# LB_BIT_o6_BUZZER-v02_rev1.net
KiCad netlist of a schematic drawn in EAGLE
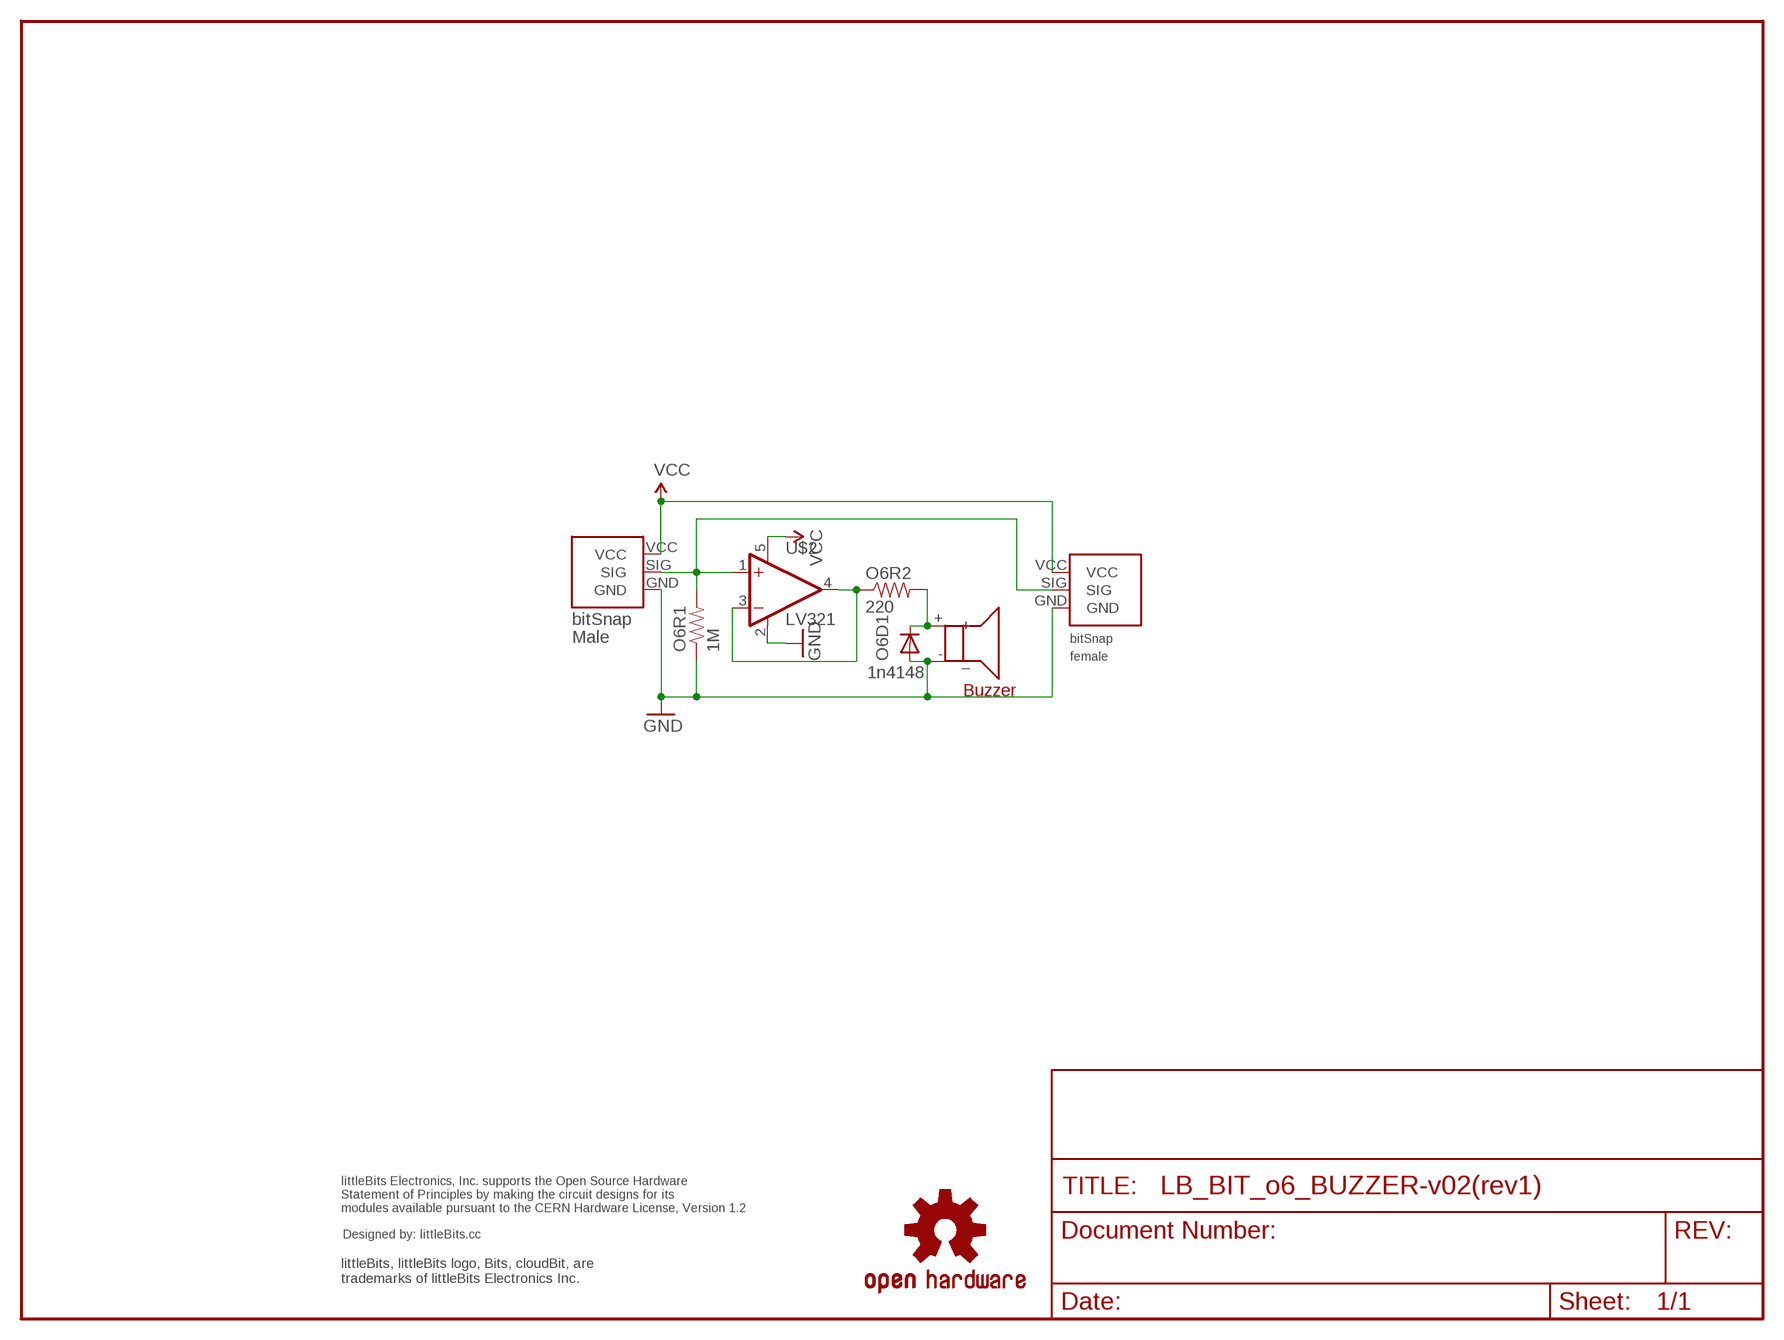
[diagram p0: schematic, sheet 1]

(export (version "E")
  (design (tool "Eeschema 10.0.6"))
  (components
    (comp (ref "O6BSF")
      (value "BITSNAP_FEMALE")
      (footprint "eagle-import:BITSNAP_FEMALE")
      (libsource (lib "eagle-import") (part "BITSNAP_FEMALE"))
    )
    (comp (ref "O6BSM")
      (value "BITSNAP_MALE")
      (footprint "eagle-import:BITSNAP_MALE")
      (libsource (lib "eagle-import") (part "BITSNAP_MALE"))
    )
    (comp (ref "O6D1")
      (value "1n4148")
      (footprint "eagle-import:SOD-323")
      (libsource (lib "eagle-import") (part "DIODESOD"))
    )
    (comp (ref "O6R1")
      (value "1M")
      (footprint "eagle-import:0603-RES")
      (libsource (lib "eagle-import") (part "RESISTOR0603-RES"))
    )
    (comp (ref "O6R2")
      (value "220")
      (footprint "eagle-import:0603-RES")
      (libsource (lib "eagle-import") (part "RESISTOR0603-RES"))
    )
    (comp (ref "O6U1")
      (value "BUZZER-JSH2317AT")
      (footprint "eagle-import:BUZZER-JSH2317AT")
      (libsource (lib "eagle-import") (part "BUZZER-JSH2317AT"))
    )
    (comp (ref "U$1")
      (value "OSHWCREDIT")
      (footprint "eagle-import:OSHWCREDIT")
      (libsource (lib "eagle-import") (part "OSHWCREDIT"))
    )
    (comp (ref "U$2")
      (value "LV321")
      (footprint "eagle-import:SC70-5")
      (libsource (lib "eagle-import") (part "LV321"))
    )
    (comp (ref "U$16")
      (value "OSHW-LOGOL")
      (footprint "eagle-import:OSHW-LOGO-L")
      (libsource (lib "eagle-import") (part "OSHW-LOGOL"))
    )
  )
  (nets
    (net (code "1") (name "GND") (class "Default")
      (node (ref "O6BSF") (pin "GND") (pinfunction "GND_GND") (pintype "bidirectional"))
      (node (ref "O6BSM") (pin "GND") (pinfunction "GND_GND") (pintype "bidirectional"))
      (node (ref "O6D1") (pin "2") (pinfunction "A_2") (pintype "passive"))
      (node (ref "O6R1") (pin "1") (pinfunction "1_1") (pintype "passive"))
      (node (ref "O6U1") (pin "-") (pinfunction "__-") (pintype "bidirectional"))
      (node (ref "U$2") (pin "2") (pinfunction "V-_2") (pintype "power_in"))
    )
    (net (code "2") (name "Net-(O6D1-C)") (class "Default")
      (node (ref "O6D1") (pin "1") (pinfunction "C_1") (pintype "passive"))
      (node (ref "O6R2") (pin "2") (pinfunction "2_2") (pintype "passive"))
      (node (ref "O6U1") (pin "+") (pinfunction "+_+") (pintype "bidirectional"))
    )
    (net (code "3") (name "Net-(U$2-+IN)") (class "Default")
      (node (ref "O6BSF") (pin "SIG") (pinfunction "SIG_SIG") (pintype "bidirectional"))
      (node (ref "O6BSM") (pin "SIG") (pinfunction "SIG_SIG") (pintype "bidirectional"))
      (node (ref "O6R1") (pin "2") (pinfunction "2_2") (pintype "passive"))
      (node (ref "U$2") (pin "1") (pinfunction "+IN_1") (pintype "input"))
    )
    (net (code "4") (name "Net-(U$2--IN)") (class "Default")
      (node (ref "O6R2") (pin "1") (pinfunction "1_1") (pintype "passive"))
      (node (ref "U$2") (pin "3") (pinfunction "-IN_3") (pintype "input"))
      (node (ref "U$2") (pin "4") (pinfunction "OUT_4") (pintype "output"))
    )
    (net (code "5") (name "VCC") (class "Default")
      (node (ref "O6BSF") (pin "VCC") (pinfunction "VCC_VCC") (pintype "bidirectional"))
      (node (ref "O6BSM") (pin "VCC") (pinfunction "VCC_VCC") (pintype "bidirectional"))
      (node (ref "U$2") (pin "5") (pinfunction "V+_5") (pintype "power_in"))
    )
  )
)
